# internal_excitation_2_w_gp.net
KiCad netlist of a schematic drawn in EAGLE
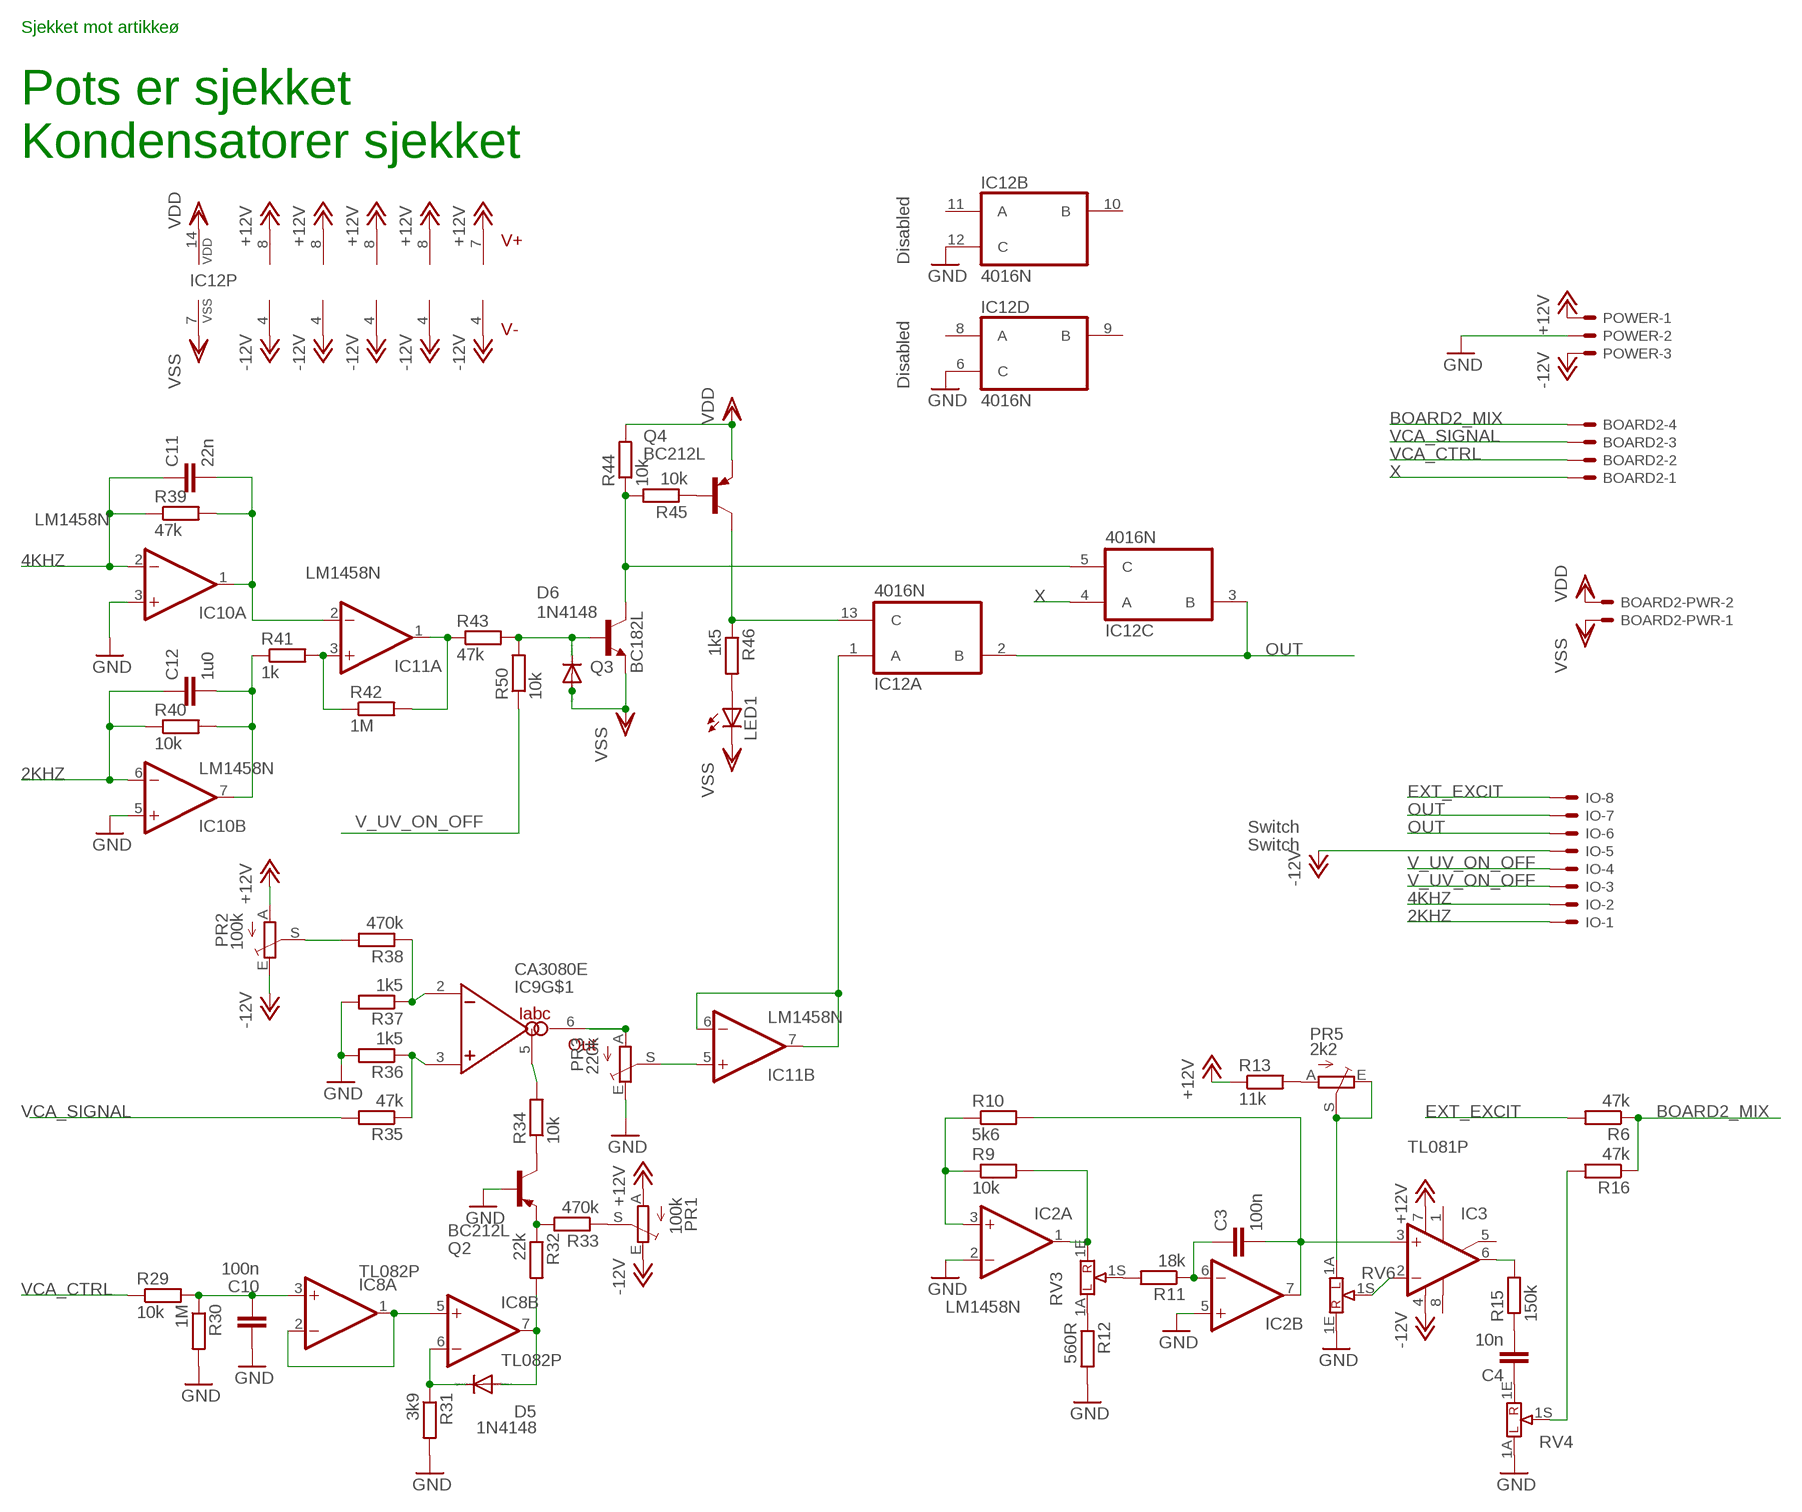
[diagram p0: schematic, sheet 1]

(export (version "E")
  (design (tool "Eeschema 10.0.6"))
  (components
    (comp (ref "BOARD2")
      (value "22-23-2041")
      (footprint "eagle-import:22-23-2041")
      (fields (field (name "MF") "MOLEX"))
      (libsource (lib "eagle-import") (part "22-23-2041"))
    )
    (comp (ref "BOARD2-PWR")
      (value "22-23-2021")
      (footprint "eagle-import:22-23-2021")
      (fields (field (name "MF") "MOLEX"))
      (libsource (lib "eagle-import") (part "22-23-2021"))
    )
    (comp (ref "C3")
      (value "100n")
      (footprint "eagle-import:C075-032X103")
      (libsource (lib "eagle-import") (part "C-EU075-032X103"))
    )
    (comp (ref "C4")
      (value "10n")
      (footprint "eagle-import:C025-025X050")
      (libsource (lib "eagle-import") (part "C-EU025-025X050"))
    )
    (comp (ref "C10")
      (value "100n")
      (footprint "eagle-import:C075-032X103")
      (libsource (lib "eagle-import") (part "C-EU075-032X103"))
    )
    (comp (ref "C11")
      (value "22n")
      (footprint "eagle-import:C050-025X075")
      (libsource (lib "eagle-import") (part "C-EU050-025X075"))
    )
    (comp (ref "C12")
      (value "1u0")
      (footprint "eagle-import:C050-025X075")
      (libsource (lib "eagle-import") (part "C-EU050-025X075"))
    )
    (comp (ref "D5")
      (value "1N4148")
      (footprint "eagle-import:DO35-5J")
      (libsource (lib "eagle-import") (part "1N4148DOJ35-5"))
    )
    (comp (ref "D6")
      (value "1N4148")
      (footprint "eagle-import:DO35-5J")
      (libsource (lib "eagle-import") (part "1N4148DOJ35-5"))
    )
    (comp (ref "IC2")
      (value "LM1458N")
      (footprint "eagle-import:DIL08")
      (libsource (lib "eagle-import") (part "1458NLM"))
    )
    (comp (ref "IC3")
      (value "TL081P")
      (footprint "eagle-import:DIL08")
      (libsource (lib "eagle-import") (part "TL081P"))
    )
    (comp (ref "IC8")
      (value "TL082P")
      (footprint "eagle-import:DIL08")
      (libsource (lib "eagle-import") (part "TL082P"))
    )
    (comp (ref "IC9")
      (value "CA3080E")
      (footprint "eagle-import:DIL08")
      (libsource (lib "eagle-import") (part "CA3080E"))
    )
    (comp (ref "IC10")
      (value "LM1458N")
      (footprint "eagle-import:DIL08")
      (libsource (lib "eagle-import") (part "1458NLM"))
    )
    (comp (ref "IC11")
      (value "LM1458N")
      (footprint "eagle-import:DIL08")
      (libsource (lib "eagle-import") (part "1458NLM"))
    )
    (comp (ref "IC12")
      (value "4016N")
      (footprint "eagle-import:DIL14")
      (libsource (lib "eagle-import") (part "4016N"))
    )
    (comp (ref "IO")
      (value "22-23-2081")
      (footprint "eagle-import:22-23-2081")
      (fields (field (name "MF") "MOLEX"))
      (libsource (lib "eagle-import") (part "22-23-2081"))
    )
    (comp (ref "LED1")
      (value "LED3MM")
      (footprint "eagle-import:LED3MM")
      (libsource (lib "eagle-import") (part "LED3MM"))
    )
    (comp (ref "POWER")
      (value "KK-156-3")
      (footprint "eagle-import:KK-156-3")
      (libsource (lib "eagle-import") (part "KK-156-3"))
    )
    (comp (ref "PR1")
      (value "100k")
      (footprint "eagle-import:CA9V")
      (libsource (lib "eagle-import") (part "TRIM_EU-CA9V"))
    )
    (comp (ref "PR2")
      (value "100k")
      (footprint "eagle-import:CA9V")
      (libsource (lib "eagle-import") (part "TRIM_EU-CA9V"))
    )
    (comp (ref "PR3")
      (value "220k")
      (footprint "eagle-import:CA9V")
      (libsource (lib "eagle-import") (part "TRIM_EU-CA9V"))
    )
    (comp (ref "PR5")
      (value "2k2")
      (footprint "eagle-import:CA9V")
      (libsource (lib "eagle-import") (part "TRIM_EU-CA9V"))
    )
    (comp (ref "Q2")
      (value "BC212L")
      (footprint "eagle-import:TO92-CBE")
      (libsource (lib "eagle-import") (part "-PNP-TO92-CBEBF493S"))
    )
    (comp (ref "Q3")
      (value "BC182L")
      (footprint "eagle-import:TO92-ECB")
      (libsource (lib "eagle-import") (part "-NPN-TO92-ECB"))
    )
    (comp (ref "Q4")
      (value "BC212L")
      (footprint "eagle-import:TO92-CBE")
      (libsource (lib "eagle-import") (part "-PNP-TO92-CBEBF493S"))
    )
    (comp (ref "R6")
      (value "47k")
      (footprint "eagle-import:0207_10")
      (libsource (lib "eagle-import") (part "R-EU_0207/10"))
    )
    (comp (ref "R9")
      (value "10k")
      (footprint "eagle-import:0207_7")
      (libsource (lib "eagle-import") (part "R-EU_0207/7"))
    )
    (comp (ref "R10")
      (value "5k6")
      (footprint "eagle-import:0207_7")
      (libsource (lib "eagle-import") (part "R-EU_0207/7"))
    )
    (comp (ref "R11")
      (value "18k")
      (footprint "eagle-import:0207_7")
      (libsource (lib "eagle-import") (part "R-EU_0207/7"))
    )
    (comp (ref "R12")
      (value "560R")
      (footprint "eagle-import:0207_7")
      (libsource (lib "eagle-import") (part "R-EU_0207/7"))
    )
    (comp (ref "R13")
      (value "11k")
      (footprint "eagle-import:0207_7")
      (libsource (lib "eagle-import") (part "R-EU_0207/7"))
    )
    (comp (ref "R15")
      (value "150k")
      (footprint "eagle-import:0207_7")
      (libsource (lib "eagle-import") (part "R-EU_0207/7"))
    )
    (comp (ref "R16")
      (value "47k")
      (footprint "eagle-import:0207_7")
      (libsource (lib "eagle-import") (part "R-EU_0207/7"))
    )
    (comp (ref "R29")
      (value "10k")
      (footprint "eagle-import:0207_7")
      (libsource (lib "eagle-import") (part "R-EU_0207/7"))
    )
    (comp (ref "R30")
      (value "1M")
      (footprint "eagle-import:0207_7")
      (libsource (lib "eagle-import") (part "R-EU_0207/7"))
    )
    (comp (ref "R31")
      (value "3k9")
      (footprint "eagle-import:0207_7")
      (libsource (lib "eagle-import") (part "R-EU_0207/7"))
    )
    (comp (ref "R32")
      (value "22k")
      (footprint "eagle-import:0207_7")
      (libsource (lib "eagle-import") (part "R-EU_0207/7"))
    )
    (comp (ref "R33")
      (value "470k")
      (footprint "eagle-import:0207_7")
      (libsource (lib "eagle-import") (part "R-EU_0207/7"))
    )
    (comp (ref "R34")
      (value "10k")
      (footprint "eagle-import:0207_7")
      (libsource (lib "eagle-import") (part "R-EU_0207/7"))
    )
    (comp (ref "R35")
      (value "47k")
      (footprint "eagle-import:0207_7")
      (libsource (lib "eagle-import") (part "R-EU_0207/7"))
    )
    (comp (ref "R36")
      (value "1k5")
      (footprint "eagle-import:0207_7")
      (libsource (lib "eagle-import") (part "R-EU_0207/7"))
    )
    (comp (ref "R37")
      (value "1k5")
      (footprint "eagle-import:0207_7")
      (libsource (lib "eagle-import") (part "R-EU_0207/7"))
    )
    (comp (ref "R38")
      (value "470k")
      (footprint "eagle-import:0207_7")
      (libsource (lib "eagle-import") (part "R-EU_0207/7"))
    )
    (comp (ref "R39")
      (value "47k")
      (footprint "eagle-import:0207_7")
      (libsource (lib "eagle-import") (part "R-EU_0207/7"))
    )
    (comp (ref "R40")
      (value "10k")
      (footprint "eagle-import:0207_7")
      (libsource (lib "eagle-import") (part "R-EU_0207/7"))
    )
    (comp (ref "R41")
      (value "1k")
      (footprint "eagle-import:0207_7")
      (libsource (lib "eagle-import") (part "R-EU_0207/7"))
    )
    (comp (ref "R42")
      (value "1M")
      (footprint "eagle-import:0207_7")
      (libsource (lib "eagle-import") (part "R-EU_0207/7"))
    )
    (comp (ref "R43")
      (value "47k")
      (footprint "eagle-import:0207_7")
      (libsource (lib "eagle-import") (part "R-EU_0207/7"))
    )
    (comp (ref "R44")
      (value "10k")
      (footprint "eagle-import:0207_7")
      (libsource (lib "eagle-import") (part "R-EU_0207/7"))
    )
    (comp (ref "R45")
      (value "10k")
      (footprint "eagle-import:0207_7")
      (libsource (lib "eagle-import") (part "R-EU_0207/7"))
    )
    (comp (ref "R46")
      (value "1k5")
      (footprint "eagle-import:0207_7")
      (libsource (lib "eagle-import") (part "R-EU_0207/7"))
    )
    (comp (ref "R50")
      (value "10k")
      (footprint "eagle-import:0207_7")
      (libsource (lib "eagle-import") (part "R-EU_0207/7"))
    )
    (comp (ref "RV3")
      (value "10k log")
      (footprint "eagle-import:POT16_W_BRACKET")
      (libsource (lib "eagle-import") (part "POT16_W_BRACKET{dblquote}{dblquote}"))
    )
    (comp (ref "RV4")
      (value "10k log")
      (footprint "eagle-import:POT16_W_BRACKET")
      (libsource (lib "eagle-import") (part "POT16_W_BRACKET{dblquote}{dblquote}"))
    )
    (comp (ref "RV6")
      (value "10k")
      (footprint "eagle-import:POT16_W_BRACKET")
      (libsource (lib "eagle-import") (part "POT16_W_BRACKET{dblquote}{dblquote}"))
    )
  )
  (nets
    (net (code "1") (name "+12V") (class "Default")
      (node (ref "IC10") (pin "8") (pinfunction "V+_8") (pintype "power_in"))
      (node (ref "IC11") (pin "8") (pinfunction "V+_8") (pintype "power_in"))
      (node (ref "IC2") (pin "8") (pinfunction "V+_8") (pintype "power_in"))
      (node (ref "IC3") (pin "7") (pinfunction "V+_7") (pintype "power_in"))
      (node (ref "IC8") (pin "8") (pinfunction "V+_8") (pintype "power_in"))
      (node (ref "IC9") (pin "7") (pinfunction "V+_7") (pintype "bidirectional"))
      (node (ref "POWER") (pin "1") (pinfunction "S_1") (pintype "passive"))
      (node (ref "PR1") (pin "A") (pinfunction "A_A") (pintype "passive"))
      (node (ref "PR2") (pin "A") (pinfunction "A_A") (pintype "passive"))
      (node (ref "R13") (pin "1") (pinfunction "1_1") (pintype "passive"))
    )
    (net (code "2") (name "-12V") (class "Default")
      (node (ref "IC10") (pin "4") (pinfunction "V-_4") (pintype "power_in"))
      (node (ref "IC11") (pin "4") (pinfunction "V-_4") (pintype "power_in"))
      (node (ref "IC2") (pin "4") (pinfunction "V-_4") (pintype "power_in"))
      (node (ref "IC3") (pin "4") (pinfunction "V-_4") (pintype "power_in"))
      (node (ref "IC8") (pin "4") (pinfunction "V-_4") (pintype "power_in"))
      (node (ref "IC9") (pin "4") (pinfunction "V-_4") (pintype "bidirectional"))
      (node (ref "IO") (pin "5") (pinfunction "S_5") (pintype "passive"))
      (node (ref "POWER") (pin "3") (pinfunction "S_3") (pintype "passive"))
      (node (ref "PR1") (pin "E") (pinfunction "E_E") (pintype "passive"))
      (node (ref "PR2") (pin "E") (pinfunction "E_E") (pintype "passive"))
    )
    (net (code "3") (name "/2KHZ") (class "Default")
      (node (ref "C12") (pin "1") (pinfunction "1_1") (pintype "passive"))
      (node (ref "IC10") (pin "6") (pinfunction "-IN_6") (pintype "input"))
      (node (ref "IO") (pin "1") (pinfunction "S_1") (pintype "passive"))
      (node (ref "R40") (pin "1") (pinfunction "1_1") (pintype "passive"))
    )
    (net (code "4") (name "/4KHZ") (class "Default")
      (node (ref "C11") (pin "1") (pinfunction "1_1") (pintype "passive"))
      (node (ref "IC10") (pin "2") (pinfunction "-IN_2") (pintype "input"))
      (node (ref "IO") (pin "2") (pinfunction "S_2") (pintype "passive"))
      (node (ref "R39") (pin "1") (pinfunction "1_1") (pintype "passive"))
    )
    (net (code "5") (name "/BOARD2_MIX") (class "Default")
      (node (ref "BOARD2") (pin "4") (pinfunction "S_4") (pintype "passive"))
      (node (ref "R16") (pin "1") (pinfunction "1_1") (pintype "passive"))
      (node (ref "R6") (pin "1") (pinfunction "1_1") (pintype "passive"))
    )
    (net (code "6") (name "/EXT_EXCIT") (class "Default")
      (node (ref "IO") (pin "8") (pinfunction "S_8") (pintype "passive"))
      (node (ref "R6") (pin "2") (pinfunction "2_2") (pintype "passive"))
    )
    (net (code "7") (name "/OUT") (class "Default")
      (node (ref "IC12") (pin "2") (pinfunction "B_2") (pintype "tri_state"))
      (node (ref "IC12") (pin "3") (pinfunction "B_3") (pintype "tri_state"))
      (node (ref "IO") (pin "6") (pinfunction "S_6") (pintype "passive"))
      (node (ref "IO") (pin "7") (pinfunction "S_7") (pintype "passive"))
    )
    (net (code "8") (name "/VCA_CTRL") (class "Default")
      (node (ref "BOARD2") (pin "2") (pinfunction "S_2") (pintype "passive"))
      (node (ref "R29") (pin "1") (pinfunction "1_1") (pintype "passive"))
    )
    (net (code "9") (name "/VCA_SIGNAL") (class "Default")
      (node (ref "BOARD2") (pin "3") (pinfunction "S_3") (pintype "passive"))
      (node (ref "R35") (pin "2") (pinfunction "2_2") (pintype "passive"))
    )
    (net (code "10") (name "/V_UV_ON_OFF") (class "Default")
      (node (ref "IO") (pin "3") (pinfunction "S_3") (pintype "passive"))
      (node (ref "IO") (pin "4") (pinfunction "S_4") (pintype "passive"))
      (node (ref "R50") (pin "1") (pinfunction "1_1") (pintype "passive"))
    )
    (net (code "11") (name "/X") (class "Default")
      (node (ref "BOARD2") (pin "1") (pinfunction "S_1") (pintype "passive"))
      (node (ref "IC12") (pin "4") (pinfunction "A_4") (pintype "tri_state"))
    )
    (net (code "12") (name "GND") (class "Default")
      (node (ref "C10") (pin "1") (pinfunction "1_1") (pintype "passive"))
      (node (ref "IC10") (pin "3") (pinfunction "+IN_3") (pintype "input"))
      (node (ref "IC10") (pin "5") (pinfunction "+IN_5") (pintype "input"))
      (node (ref "IC12") (pin "12") (pinfunction "C_12") (pintype "input"))
      (node (ref "IC12") (pin "6") (pinfunction "C_6") (pintype "input"))
      (node (ref "IC2") (pin "2") (pinfunction "-IN_2") (pintype "input"))
      (node (ref "IC2") (pin "5") (pinfunction "+IN_5") (pintype "input"))
      (node (ref "POWER") (pin "2") (pinfunction "S_2") (pintype "passive"))
      (node (ref "PR3") (pin "E") (pinfunction "E_E") (pintype "passive"))
      (node (ref "Q2") (pin "B") (pinfunction "B_B") (pintype "passive"))
      (node (ref "R12") (pin "2") (pinfunction "2_2") (pintype "passive"))
      (node (ref "R30") (pin "2") (pinfunction "2_2") (pintype "passive"))
      (node (ref "R31") (pin "2") (pinfunction "2_2") (pintype "passive"))
      (node (ref "R36") (pin "2") (pinfunction "2_2") (pintype "passive"))
      (node (ref "R37") (pin "2") (pinfunction "2_2") (pintype "passive"))
      (node (ref "RV4") (pin "1A") (pinfunction "1A_1A") (pintype "passive"))
      (node (ref "RV6") (pin "1E") (pinfunction "1E_1E") (pintype "passive"))
    )
    (net (code "13") (name "Net-(C4-Pad1)") (class "Default")
      (node (ref "C4") (pin "1") (pinfunction "1_1") (pintype "passive"))
      (node (ref "RV4") (pin "1E") (pinfunction "1E_1E") (pintype "passive"))
    )
    (net (code "14") (name "Net-(C4-Pad2)") (class "Default")
      (node (ref "C4") (pin "2") (pinfunction "2_2") (pintype "passive"))
      (node (ref "R15") (pin "1") (pinfunction "1_1") (pintype "passive"))
    )
    (net (code "15") (name "Net-(D6-PadC)") (class "Default")
      (node (ref "D6") (pin "C") (pinfunction "C_C") (pintype "passive"))
      (node (ref "Q3") (pin "B") (pinfunction "B_B") (pintype "passive"))
      (node (ref "R43") (pin "2") (pinfunction "2_2") (pintype "passive"))
      (node (ref "R50") (pin "2") (pinfunction "2_2") (pintype "passive"))
    )
    (net (code "16") (name "Net-(IC2A-+IN)") (class "Default")
      (node (ref "IC2") (pin "3") (pinfunction "+IN_3") (pintype "input"))
      (node (ref "R10") (pin "1") (pinfunction "1_1") (pintype "passive"))
      (node (ref "R9") (pin "1") (pinfunction "1_1") (pintype "passive"))
    )
    (net (code "17") (name "Net-(IC2A-OUT)") (class "Default")
      (node (ref "IC2") (pin "1") (pinfunction "OUT_1") (pintype "output"))
      (node (ref "R9") (pin "2") (pinfunction "2_2") (pintype "passive"))
      (node (ref "RV3") (pin "1E") (pinfunction "1E_1E") (pintype "passive"))
    )
    (net (code "18") (name "Net-(IC2B--IN)") (class "Default")
      (node (ref "C3") (pin "1") (pinfunction "1_1") (pintype "passive"))
      (node (ref "IC2") (pin "6") (pinfunction "-IN_6") (pintype "input"))
      (node (ref "R11") (pin "1") (pinfunction "1_1") (pintype "passive"))
    )
    (net (code "19") (name "Net-(IC2B-OUT)") (class "Default")
      (node (ref "C3") (pin "2") (pinfunction "2_2") (pintype "passive"))
      (node (ref "IC2") (pin "7") (pinfunction "OUT_7") (pintype "output"))
      (node (ref "IC3") (pin "3") (pinfunction "+IN_3") (pintype "input"))
      (node (ref "R10") (pin "2") (pinfunction "2_2") (pintype "passive"))
    )
    (net (code "20") (name "Net-(IC3--IN)") (class "Default")
      (node (ref "IC3") (pin "2") (pinfunction "-IN_2") (pintype "input"))
      (node (ref "RV6") (pin "1S") (pinfunction "1S_1S") (pintype "passive"))
    )
    (net (code "21") (name "Net-(IC3-OUT)") (class "Default")
      (node (ref "IC3") (pin "6") (pinfunction "OUT_6") (pintype "output"))
      (node (ref "R15") (pin "2") (pinfunction "2_2") (pintype "passive"))
    )
    (net (code "22") (name "Net-(IC8A-+IN)") (class "Default")
      (node (ref "C10") (pin "2") (pinfunction "2_2") (pintype "passive"))
      (node (ref "IC8") (pin "3") (pinfunction "+IN_3") (pintype "input"))
      (node (ref "R29") (pin "2") (pinfunction "2_2") (pintype "passive"))
      (node (ref "R30") (pin "1") (pinfunction "1_1") (pintype "passive"))
    )
    (net (code "23") (name "Net-(IC8A--IN)") (class "Default")
      (node (ref "IC8") (pin "1") (pinfunction "OUT_1") (pintype "output"))
      (node (ref "IC8") (pin "2") (pinfunction "-IN_2") (pintype "input"))
      (node (ref "IC8") (pin "5") (pinfunction "+IN_5") (pintype "input"))
    )
    (net (code "24") (name "Net-(IC8B--IN)") (class "Default")
      (node (ref "D5") (pin "C") (pinfunction "C_C") (pintype "passive"))
      (node (ref "IC8") (pin "6") (pinfunction "-IN_6") (pintype "input"))
      (node (ref "R31") (pin "1") (pinfunction "1_1") (pintype "passive"))
    )
    (net (code "25") (name "Net-(IC8B-OUT)") (class "Default")
      (node (ref "D5") (pin "A") (pinfunction "A_A") (pintype "passive"))
      (node (ref "IC8") (pin "7") (pinfunction "OUT_7") (pintype "output"))
      (node (ref "R32") (pin "2") (pinfunction "2_2") (pintype "passive"))
    )
    (net (code "26") (name "Net-(IC9A-+IN)") (class "Default")
      (node (ref "IC9") (pin "3") (pinfunction "+IN_3") (pintype "bidirectional"))
      (node (ref "R35") (pin "1") (pinfunction "1_1") (pintype "passive"))
      (node (ref "R36") (pin "1") (pinfunction "1_1") (pintype "passive"))
    )
    (net (code "27") (name "Net-(IC9A--IN)") (class "Default")
      (node (ref "IC9") (pin "2") (pinfunction "-IN_2") (pintype "bidirectional"))
      (node (ref "R37") (pin "1") (pinfunction "1_1") (pintype "passive"))
      (node (ref "R38") (pin "1") (pinfunction "1_1") (pintype "passive"))
    )
    (net (code "28") (name "Net-(IC9A-IABC)") (class "Default")
      (node (ref "IC9") (pin "5") (pinfunction "IABC_5") (pintype "bidirectional"))
      (node (ref "R34") (pin "2") (pinfunction "2_2") (pintype "passive"))
    )
    (net (code "29") (name "Net-(IC9A-OUT)") (class "Default")
      (node (ref "IC9") (pin "6") (pinfunction "OUT_6") (pintype "bidirectional"))
      (node (ref "PR3") (pin "A") (pinfunction "A_A") (pintype "passive"))
    )
    (net (code "30") (name "Net-(IC10A-OUT)") (class "Default")
      (node (ref "C11") (pin "2") (pinfunction "2_2") (pintype "passive"))
      (node (ref "IC10") (pin "1") (pinfunction "OUT_1") (pintype "output"))
      (node (ref "IC11") (pin "2") (pinfunction "-IN_2") (pintype "input"))
      (node (ref "R39") (pin "2") (pinfunction "2_2") (pintype "passive"))
    )
    (net (code "31") (name "Net-(IC10B-OUT)") (class "Default")
      (node (ref "C12") (pin "2") (pinfunction "2_2") (pintype "passive"))
      (node (ref "IC10") (pin "7") (pinfunction "OUT_7") (pintype "output"))
      (node (ref "R40") (pin "2") (pinfunction "2_2") (pintype "passive"))
      (node (ref "R41") (pin "1") (pinfunction "1_1") (pintype "passive"))
    )
    (net (code "32") (name "Net-(IC11A-+IN)") (class "Default")
      (node (ref "IC11") (pin "3") (pinfunction "+IN_3") (pintype "input"))
      (node (ref "R41") (pin "2") (pinfunction "2_2") (pintype "passive"))
      (node (ref "R42") (pin "1") (pinfunction "1_1") (pintype "passive"))
    )
    (net (code "33") (name "Net-(IC11A-OUT)") (class "Default")
      (node (ref "IC11") (pin "1") (pinfunction "OUT_1") (pintype "output"))
      (node (ref "R42") (pin "2") (pinfunction "2_2") (pintype "passive"))
      (node (ref "R43") (pin "1") (pinfunction "1_1") (pintype "passive"))
    )
    (net (code "34") (name "Net-(IC11B-+IN)") (class "Default")
      (node (ref "IC11") (pin "5") (pinfunction "+IN_5") (pintype "input"))
      (node (ref "PR3") (pin "S") (pinfunction "S_S") (pintype "passive"))
    )
    (net (code "35") (name "Net-(IC11B--IN)") (class "Default")
      (node (ref "IC11") (pin "6") (pinfunction "-IN_6") (pintype "input"))
      (node (ref "IC11") (pin "7") (pinfunction "OUT_7") (pintype "output"))
      (node (ref "IC12") (pin "1") (pinfunction "A_1") (pintype "tri_state"))
    )
    (net (code "36") (name "Net-(IC12A-C)") (class "Default")
      (node (ref "IC12") (pin "13") (pinfunction "C_13") (pintype "input"))
      (node (ref "Q4") (pin "C") (pinfunction "C_C") (pintype "passive"))
      (node (ref "R46") (pin "1") (pinfunction "1_1") (pintype "passive"))
    )
    (net (code "37") (name "Net-(IC12C-C)") (class "Default")
      (node (ref "IC12") (pin "5") (pinfunction "C_5") (pintype "input"))
      (node (ref "Q3") (pin "C") (pinfunction "C_C") (pintype "passive"))
      (node (ref "R44") (pin "1") (pinfunction "1_1") (pintype "passive"))
      (node (ref "R45") (pin "2") (pinfunction "2_2") (pintype "passive"))
    )
    (net (code "38") (name "Net-(LED1-PadA)") (class "Default")
      (node (ref "LED1") (pin "A") (pinfunction "A_A") (pintype "passive"))
      (node (ref "R46") (pin "2") (pinfunction "2_2") (pintype "passive"))
    )
    (net (code "39") (name "Net-(PR1-PadS)") (class "Default")
      (node (ref "PR1") (pin "S") (pinfunction "S_S") (pintype "passive"))
      (node (ref "R33") (pin "1") (pinfunction "1_1") (pintype "passive"))
    )
    (net (code "40") (name "Net-(PR2-PadS)") (class "Default")
      (node (ref "PR2") (pin "S") (pinfunction "S_S") (pintype "passive"))
      (node (ref "R38") (pin "2") (pinfunction "2_2") (pintype "passive"))
    )
    (net (code "41") (name "Net-(PR5-PadA)") (class "Default")
      (node (ref "PR5") (pin "A") (pinfunction "A_A") (pintype "passive"))
      (node (ref "R13") (pin "2") (pinfunction "2_2") (pintype "passive"))
    )
    (net (code "42") (name "Net-(PR5-PadE)") (class "Default")
      (node (ref "PR5") (pin "E") (pinfunction "E_E") (pintype "passive"))
      (node (ref "PR5") (pin "S") (pinfunction "S_S") (pintype "passive"))
      (node (ref "RV6") (pin "1A") (pinfunction "1A_1A") (pintype "passive"))
    )
    (net (code "43") (name "Net-(Q2-PadC)") (class "Default")
      (node (ref "Q2") (pin "C") (pinfunction "C_C") (pintype "passive"))
      (node (ref "R34") (pin "1") (pinfunction "1_1") (pintype "passive"))
    )
    (net (code "44") (name "Net-(Q2-PadE)") (class "Default")
      (node (ref "Q2") (pin "E") (pinfunction "E_E") (pintype "passive"))
      (node (ref "R32") (pin "1") (pinfunction "1_1") (pintype "passive"))
      (node (ref "R33") (pin "2") (pinfunction "2_2") (pintype "passive"))
    )
    (net (code "45") (name "Net-(Q4-PadB)") (class "Default")
      (node (ref "Q4") (pin "B") (pinfunction "B_B") (pintype "passive"))
      (node (ref "R45") (pin "1") (pinfunction "1_1") (pintype "passive"))
    )
    (net (code "46") (name "Net-(R11-Pad2)") (class "Default")
      (node (ref "R11") (pin "2") (pinfunction "2_2") (pintype "passive"))
      (node (ref "RV3") (pin "1S") (pinfunction "1S_1S") (pintype "passive"))
    )
    (net (code "47") (name "Net-(R12-Pad1)") (class "Default")
      (node (ref "R12") (pin "1") (pinfunction "1_1") (pintype "passive"))
      (node (ref "RV3") (pin "1A") (pinfunction "1A_1A") (pintype "passive"))
    )
    (net (code "48") (name "Net-(R16-Pad2)") (class "Default")
      (node (ref "R16") (pin "2") (pinfunction "2_2") (pintype "passive"))
      (node (ref "RV4") (pin "1S") (pinfunction "1S_1S") (pintype "passive"))
    )
    (net (code "49") (name "VDD") (class "Default")
      (node (ref "BOARD2-PWR") (pin "2") (pinfunction "S_2") (pintype "passive"))
      (node (ref "IC12") (pin "14") (pinfunction "VDD_14") (pintype "power_in"))
      (node (ref "Q4") (pin "E") (pinfunction "E_E") (pintype "passive"))
      (node (ref "R44") (pin "2") (pinfunction "2_2") (pintype "passive"))
    )
    (net (code "50") (name "VSS") (class "Default")
      (node (ref "BOARD2-PWR") (pin "1") (pinfunction "S_1") (pintype "passive"))
      (node (ref "D6") (pin "A") (pinfunction "A_A") (pintype "passive"))
      (node (ref "IC12") (pin "7") (pinfunction "VSS_7") (pintype "power_in"))
      (node (ref "LED1") (pin "K") (pinfunction "C_K") (pintype "passive"))
      (node (ref "Q3") (pin "E") (pinfunction "E_E") (pintype "passive"))
    )
    (net (code "51") (name "unconnected-(IC3-ON1-Pad1)") (class "Default")
      (node (ref "IC3") (pin "1") (pinfunction "ON1_1") (pintype "passive"))
    )
    (net (code "52") (name "unconnected-(IC3-ON2-Pad5)") (class "Default")
      (node (ref "IC3") (pin "5") (pinfunction "ON2_5") (pintype "passive"))
    )
    (net (code "53") (name "unconnected-(IC3-OPT-Pad8)") (class "Default")
      (node (ref "IC3") (pin "8") (pinfunction "OPT_8") (pintype "passive"))
    )
    (net (code "54") (name "unconnected-(IC12B-A-Pad11)") (class "Default")
      (node (ref "IC12") (pin "11") (pinfunction "A_11") (pintype "tri_state"))
    )
    (net (code "55") (name "unconnected-(IC12B-B-Pad10)") (class "Default")
      (node (ref "IC12") (pin "10") (pinfunction "B_10") (pintype "tri_state"))
    )
    (net (code "56") (name "unconnected-(IC12D-A-Pad8)") (class "Default")
      (node (ref "IC12") (pin "8") (pinfunction "A_8") (pintype "tri_state"))
    )
    (net (code "57") (name "unconnected-(IC12D-B-Pad9)") (class "Default")
      (node (ref "IC12") (pin "9") (pinfunction "B_9") (pintype "tri_state"))
    )
  )
)
